# Trap_PCB_SMT2024.net
KiCad netlist of a schematic drawn in Altium Designer
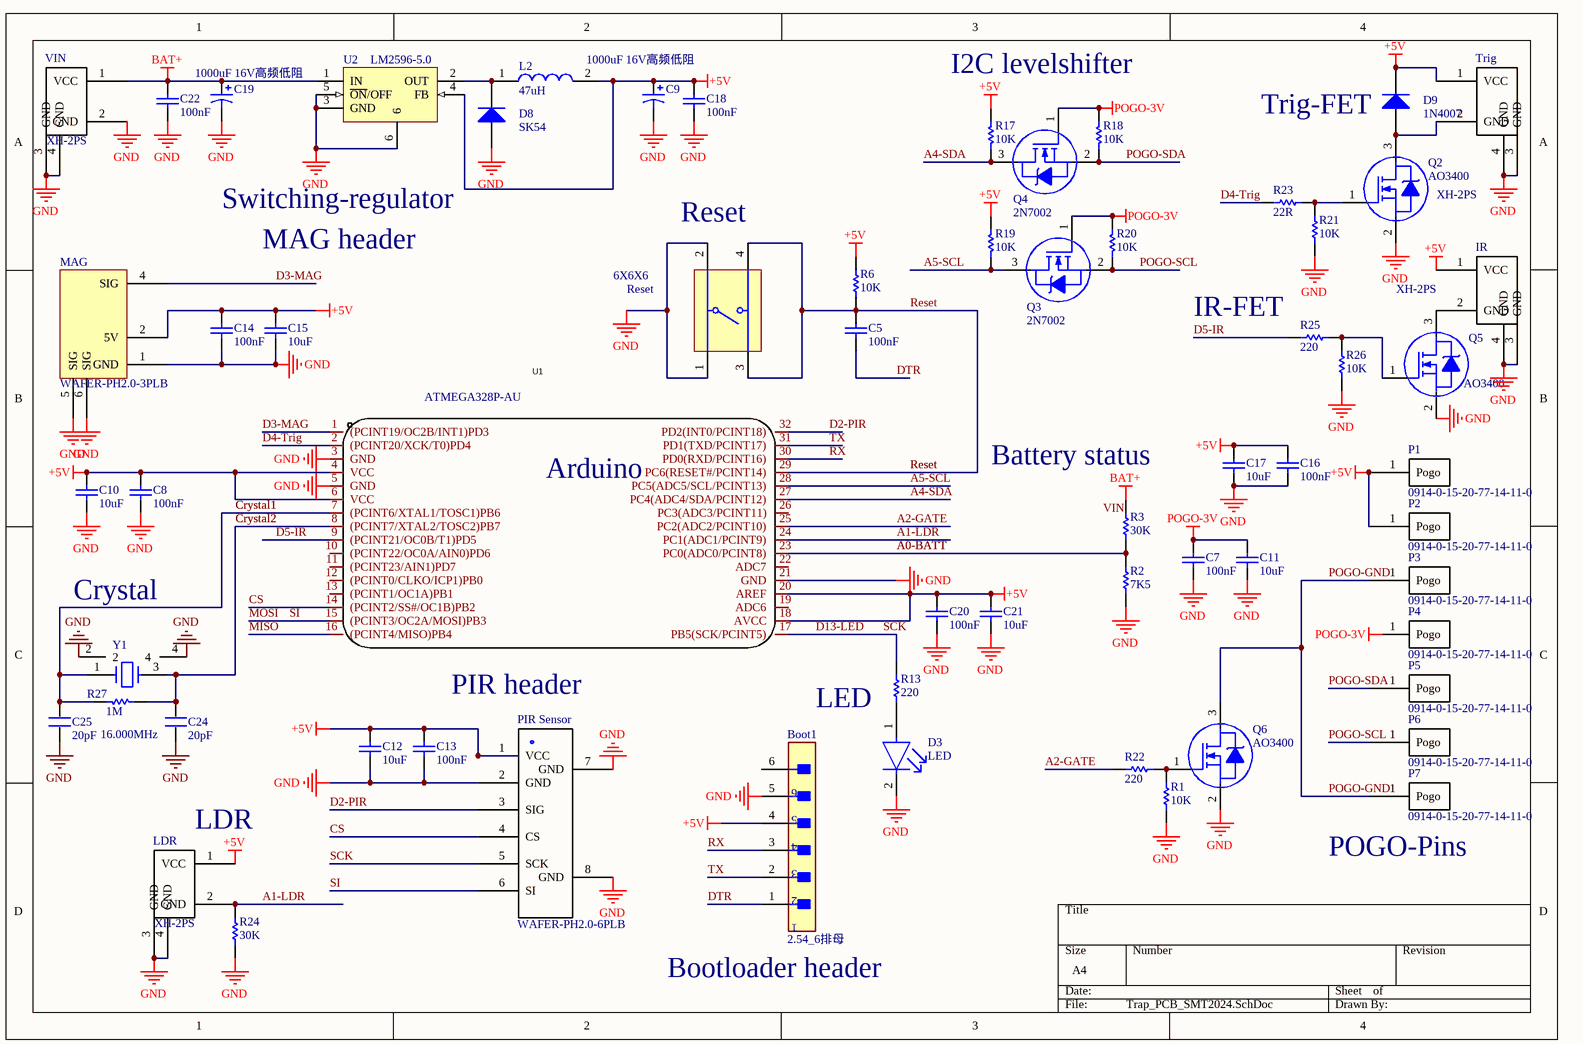
[diagram p0: Trap_PCB_SMT2024.SchDoc]

(export (version "E")
  (design (tool "Eeschema 10.0.6"))
  (components
    (comp (ref "Boot1")
      (value "2.54_6排母")
      (footprint "FP-SWR25X-NRTC-S06-ST-BA-MFG")
      (description "CONN HEADER VERT 6POS 2.54MM")
      (fields
        (field (name "OCTOPART") "https://octopart.com/swr25x-nrtc-s06-st-ba-sullins-20912730")
        (field (name "MANUFACTURER") "Sullins")
      )
      (libsource (lib "*") (part "f2cb566baf1c37ab5a3b8e90bbeafd6"))
    )
    (comp (ref "C5")
      (value "100nF")
      (footprint "0603C")
      (description "Capacitor, Ceramic, 22 pF, +/-10 %, 100 V, -55 to 125 degC, 2-Pin THD, RoHS, Bulk")
      (libsource (lib "*") (part "CAP-NP-2"))
    )
    (comp (ref "C7")
      (value "100nF")
      (footprint "0603C")
      (description "Capacitor, Ceramic, 22 pF, +/-10 %, 100 V, -55 to 125 degC, 2-Pin THD, RoHS, Bulk")
      (libsource (lib "*") (part "CAP-NP-2"))
    )
    (comp (ref "C8")
      (value "100nF")
      (footprint "0603C")
      (description "Capacitor, Ceramic, 22 pF, +/-10 %, 100 V, -55 to 125 degC, 2-Pin THD, RoHS, Bulk")
      (libsource (lib "*") (part "CAP-NP-2"))
    )
    (comp (ref "C9")
      (value "1000uF 16V高频低阻")
      (footprint "CAP-SMD_BD10.0-L10.3-W10.3-LS11.3-FD")
      (description "Polarized Capacitor (Surface Mount)")
      (fields (field (name "PUBLISHER") "Altium Limited"))
      (libsource (lib "Miscellaneous Devices") (part "Cap Pol3"))
    )
    (comp (ref "C10")
      (value "10uF")
      (footprint "0603C")
      (description "Capacitor, Ceramic, 22 pF, +/-10 %, 100 V, -55 to 125 degC, 2-Pin THD, RoHS, Bulk")
      (libsource (lib "*") (part "CAP-NP-2"))
    )
    (comp (ref "C11")
      (value "10uF")
      (footprint "0603C")
      (description "Capacitor, Ceramic, 22 pF, +/-10 %, 100 V, -55 to 125 degC, 2-Pin THD, RoHS, Bulk")
      (libsource (lib "*") (part "CAP-NP-2"))
    )
    (comp (ref "C12")
      (value "10uF")
      (footprint "0603C")
      (description "Capacitor, Ceramic, 22 pF, +/-10 %, 100 V, -55 to 125 degC, 2-Pin THD, RoHS, Bulk")
      (libsource (lib "*") (part "CAP-NP-2"))
    )
    (comp (ref "C13")
      (value "100nF")
      (footprint "0603C")
      (description "Capacitor, Ceramic, 22 pF, +/-10 %, 100 V, -55 to 125 degC, 2-Pin THD, RoHS, Bulk")
      (libsource (lib "*") (part "CAP-NP-2"))
    )
    (comp (ref "C14")
      (value "100nF")
      (footprint "0603C")
      (description "Capacitor, Ceramic, 22 pF, +/-10 %, 100 V, -55 to 125 degC, 2-Pin THD, RoHS, Bulk")
      (libsource (lib "*") (part "CAP-NP-2"))
    )
    (comp (ref "C15")
      (value "10uF")
      (footprint "0603C")
      (description "Capacitor, Ceramic, 22 pF, +/-10 %, 100 V, -55 to 125 degC, 2-Pin THD, RoHS, Bulk")
      (libsource (lib "*") (part "CAP-NP-2"))
    )
    (comp (ref "C16")
      (value "100nF")
      (footprint "0603C")
      (description "Capacitor, Ceramic, 22 pF, +/-10 %, 100 V, -55 to 125 degC, 2-Pin THD, RoHS, Bulk")
      (libsource (lib "*") (part "CAP-NP-2"))
    )
    (comp (ref "C17")
      (value "10uF")
      (footprint "0603C")
      (description "Capacitor, Ceramic, 22 pF, +/-10 %, 100 V, -55 to 125 degC, 2-Pin THD, RoHS, Bulk")
      (libsource (lib "*") (part "CAP-NP-2"))
    )
    (comp (ref "C18")
      (value "100nF")
      (footprint "0603C")
      (description "贴片")
      (libsource (lib "Schlib1") (part "电容"))
    )
    (comp (ref "C19")
      (value "1000uF 16V高频低阻")
      (footprint "CAP-SMD_BD10.0-L10.3-W10.3-LS11.3-FD")
      (description "Polarized Capacitor (Surface Mount)")
      (fields (field (name "PUBLISHER") "Altium Limited"))
      (libsource (lib "Miscellaneous Devices") (part "Cap Pol3"))
    )
    (comp (ref "C20")
      (value "100nF")
      (footprint "0603C")
      (description "Capacitor, Ceramic, 22 pF, +/-10 %, 100 V, -55 to 125 degC, 2-Pin THD, RoHS, Bulk")
      (libsource (lib "*") (part "CAP-NP-2"))
    )
    (comp (ref "C21")
      (value "10uF")
      (footprint "0603C")
      (description "Capacitor, Ceramic, 22 pF, +/-10 %, 100 V, -55 to 125 degC, 2-Pin THD, RoHS, Bulk")
      (libsource (lib "*") (part "CAP-NP-2"))
    )
    (comp (ref "C22")
      (value "100nF")
      (footprint "0603C")
      (description "贴片")
      (libsource (lib "Schlib1") (part "电容"))
    )
    (comp (ref "C24") (value "20pF") (footprint "0603C") (libsource (lib "*") (part "C")))
    (comp (ref "C25") (value "20pF") (footprint "0603C") (libsource (lib "*") (part "C")))
    (comp (ref "D3")
      (value "LED")
      (footprint "0603LED")
      (description "LED YELLOW DIFFUSED T-1 T/H")
      (fields (field (name "MANUFACTURER") "Broadcom"))
      (libsource (lib "*") (part "8706943c75ba83719d021d2fdc84c58"))
    )
    (comp (ref "D8")
      (value "SK54")
      (footprint "SMB-K")
      (description "Default Diode")
      (fields (field (name "PUBLISHER") "Altium Limited"))
      (libsource (lib "*") (part "Diode"))
    )
    (comp (ref "D9")
      (value "1N4007")
      (footprint "SMA")
      (description "Default Diode")
      (fields (field (name "PUBLISHER") "Altium Limited"))
      (libsource (lib "*") (part "Diode"))
    )
    (comp (ref "IR") (value "XH-2PS") (footprint "CNS_2.5-2") (libsource (lib "*") (part "JST HXP2")))
    (comp (ref "L2")
      (value "47uH")
      (footprint "L10.8X10")
      (description "Inductor")
      (fields (field (name "MANUFACTURER_PART_NUMBER") "SPM6545VT-100M-D"))
      (libsource (lib "*") (part "SPM6545VT-100M-D"))
    )
    (comp (ref "LDR") (value "XH-2PS") (footprint "CNS_2.5-2") (libsource (lib "*") (part "JST HXP2")))
    (comp (ref "MAG")
      (value "WAFER-PH2.0-3PLB")
      (footprint "CNS-2.0-4")
      (libsource (lib "*") (part "MAG Sensor"))
    )
    (comp (ref "P1")
      (value "0914-0-15-20-77-14-11-0")
      (footprint "0914-0-15-20-77-14-11-0")
      (description "CONTACT SPRING LOADED T/H GOLD")
      (libsource (lib "*") (part "0914-0-15-20-77-14-11-0"))
    )
    (comp (ref "P2")
      (value "0914-0-15-20-77-14-11-0")
      (footprint "0914-0-15-20-77-14-11-0")
      (description "CONTACT SPRING LOADED T/H GOLD")
      (libsource (lib "*") (part "0914-0-15-20-77-14-11-0"))
    )
    (comp (ref "P3")
      (value "0914-0-15-20-77-14-11-0")
      (footprint "0914-0-15-20-77-14-11-0")
      (description "CONTACT SPRING LOADED T/H GOLD")
      (libsource (lib "*") (part "0914-0-15-20-77-14-11-0"))
    )
    (comp (ref "P4")
      (value "0914-0-15-20-77-14-11-0")
      (footprint "0914-0-15-20-77-14-11-0")
      (description "CONTACT SPRING LOADED T/H GOLD")
      (libsource (lib "*") (part "0914-0-15-20-77-14-11-0"))
    )
    (comp (ref "P5")
      (value "0914-0-15-20-77-14-11-0")
      (footprint "0914-0-15-20-77-14-11-0")
      (description "CONTACT SPRING LOADED T/H GOLD")
      (libsource (lib "*") (part "0914-0-15-20-77-14-11-0"))
    )
    (comp (ref "P6")
      (value "0914-0-15-20-77-14-11-0")
      (footprint "0914-0-15-20-77-14-11-0")
      (description "CONTACT SPRING LOADED T/H GOLD")
      (libsource (lib "*") (part "0914-0-15-20-77-14-11-0"))
    )
    (comp (ref "P7")
      (value "0914-0-15-20-77-14-11-0")
      (footprint "0914-0-15-20-77-14-11-0")
      (description "CONTACT SPRING LOADED T/H GOLD")
      (libsource (lib "*") (part "0914-0-15-20-77-14-11-0"))
    )
    (comp (ref "PIR Sensor")
      (value "WAFER-PH2.0-6PLB")
      (footprint "CNS-2.0-6")
      (libsource (lib "*") (part "JST - PH-6p - 2.0mm"))
    )
    (comp (ref "Q2") (value "AO3400") (footprint "SOT-23") (libsource (lib "Schlib1") (part "IRF640N")))
    (comp (ref "Q3") (value "2N7002") (footprint "SOT-23") (libsource (lib "") (part "IRF640N_1")))
    (comp (ref "Q4") (value "2N7002") (footprint "SOT-23") (libsource (lib "") (part "IRF640N_1")))
    (comp (ref "Q5") (value "AO3400") (footprint "SOT-23") (libsource (lib "Schlib1") (part "IRF640N")))
    (comp (ref "Q6") (value "AO3400") (footprint "SOT-23") (libsource (lib "Schlib1") (part "IRF640N")))
    (comp (ref "R1")
      (value "10K")
      (footprint "0603R")
      (fields (field (name "TOLERANCE") "±5%"))
      (libsource (lib "*") (part "RES-2"))
    )
    (comp (ref "R2")
      (value "7K5")
      (footprint "0603R")
      (fields (field (name "TOLERANCE") "±5%"))
      (libsource (lib "*") (part "RES-2"))
    )
    (comp (ref "R3")
      (value "30K")
      (footprint "0603R")
      (fields (field (name "TOLERANCE") "±5%"))
      (libsource (lib "*") (part "RES-2"))
    )
    (comp (ref "R6")
      (value "10K")
      (footprint "0603R")
      (fields (field (name "TOLERANCE") "±5%"))
      (libsource (lib "*") (part "RES-2"))
    )
    (comp (ref "R13")
      (value "220")
      (footprint "0603R")
      (fields (field (name "TOLERANCE") "±5%"))
      (libsource (lib "*") (part "RES-2"))
    )
    (comp (ref "R17")
      (value "10K")
      (footprint "0603R")
      (fields (field (name "TOLERANCE") "±5%"))
      (libsource (lib "*") (part "RES-2"))
    )
    (comp (ref "R18")
      (value "10K")
      (footprint "0603R")
      (fields (field (name "TOLERANCE") "±5%"))
      (libsource (lib "*") (part "RES-2"))
    )
    (comp (ref "R19")
      (value "10K")
      (footprint "0603R")
      (fields (field (name "TOLERANCE") "±5%"))
      (libsource (lib "*") (part "RES-2"))
    )
    (comp (ref "R20")
      (value "10K")
      (footprint "0603R")
      (fields (field (name "TOLERANCE") "±5%"))
      (libsource (lib "*") (part "RES-2"))
    )
    (comp (ref "R21")
      (value "10K")
      (footprint "0603R")
      (fields (field (name "TOLERANCE") "±5%"))
      (libsource (lib "*") (part "RES-2"))
    )
    (comp (ref "R22")
      (value "220")
      (footprint "0603R")
      (fields (field (name "TOLERANCE") "±5%"))
      (libsource (lib "*") (part "RES-2"))
    )
    (comp (ref "R23")
      (value "22R")
      (footprint "0603R")
      (fields (field (name "TOLERANCE") "±5%"))
      (libsource (lib "*") (part "RES-2"))
    )
    (comp (ref "R24")
      (value "30K")
      (footprint "0603R")
      (fields (field (name "TOLERANCE") "±5%"))
      (libsource (lib "*") (part "RES-2"))
    )
    (comp (ref "R25")
      (value "220")
      (footprint "0603R")
      (fields (field (name "TOLERANCE") "±5%"))
      (libsource (lib "*") (part "RES-2"))
    )
    (comp (ref "R26")
      (value "10K")
      (footprint "0603R")
      (fields (field (name "TOLERANCE") "±5%"))
      (libsource (lib "*") (part "RES-2"))
    )
    (comp (ref "R27")
      (value "1M")
      (footprint "0603R")
      (description "Resistor")
      (fields (field (name "PUBLISHER") "Altium Limited"))
      (libsource (lib "Miscellaneous Devices") (part "Res1"))
    )
    (comp (ref "Reset")
      (value "6X6X6")
      (footprint "SW-4P-6X6")
      (description "Tactile Switch, SPST-NO, 0.05 A, 5 to 24 V, -25 to 70 degC, 4-Pin THD, RoHS, Bulk")
      (libsource (lib "*") (part "SW-SPST-4_A"))
    )
    (comp (ref "Trig") (value "XH-2PS") (footprint "CNS_2.5-2") (libsource (lib "*") (part "JST HXP2")))
    (comp (ref "U1")
      (value "ATMEGA328P-AU")
      (footprint "TQFP-32_L7.0-W7.0-P0.80-LS9.0-BL")
      (libsource (lib "altium-import") (part "root_0_ATMEGA328P-AU_"))
    )
    (comp (ref "U2")
      (value "LM2596-5.0")
      (footprint "TO263-5")
      (description "Simple Switcher Power Converter 150 kHz 3A Step Down Voltage Regulator")
      (fields (field (name "PUBLISHER") "Altium Limited"))
      (libsource (lib "NSC Power Mgt Switching Regulator") (part "LM2596T-5.0"))
    )
    (comp (ref "VIN") (value "XH-2PS") (footprint "CNS_2.5-2") (libsource (lib "*") (part "JST HXP2")))
    (comp (ref "Y1")
      (value "16.000MHz")
      (footprint "X3225")
      (description "R25010031/工业C/消费A/晶体振荡器/8.000M/20pF/±30ppm/49USM/ROHS/-10℃~+70℃")
      (libsource (lib "R25_IC") (part "R25010031"))
    )
  )
  (nets
    (net (code "1") (name "+5V") (class "Default")
      (node (ref "Boot1") (pin "4") (pinfunction "4_4") (pintype "passive"))
      (node (ref "C10") (pin "2") (pinfunction "2_2") (pintype "passive"))
      (node (ref "C12") (pin "2") (pinfunction "2_2") (pintype "passive"))
      (node (ref "C13") (pin "2") (pinfunction "2_2") (pintype "passive"))
      (node (ref "C14") (pin "2") (pinfunction "2_2") (pintype "passive"))
      (node (ref "C15") (pin "2") (pinfunction "2_2") (pintype "passive"))
      (node (ref "C16") (pin "2") (pinfunction "2_2") (pintype "passive"))
      (node (ref "C17") (pin "2") (pinfunction "2_2") (pintype "passive"))
      (node (ref "C18") (pin "1") (pinfunction "1_1") (pintype "passive"))
      (node (ref "C20") (pin "2") (pinfunction "2_2") (pintype "passive"))
      (node (ref "C21") (pin "2") (pinfunction "2_2") (pintype "passive"))
      (node (ref "C8") (pin "2") (pinfunction "2_2") (pintype "passive"))
      (node (ref "C9") (pin "1") (pinfunction "1_1") (pintype "passive"))
      (node (ref "D9") (pin "2") (pinfunction "K_2") (pintype "passive"))
      (node (ref "IR") (pin "1") (pinfunction "VCC_1") (pintype "passive"))
      (node (ref "L2") (pin "2") (pinfunction "2_2") (pintype "passive"))
      (node (ref "LDR") (pin "1") (pinfunction "VCC_1") (pintype "passive"))
      (node (ref "MAG") (pin "2") (pinfunction "5V_2") (pintype "passive"))
      (node (ref "P1") (pin "1") (pinfunction "Pogo_1") (pintype "passive"))
      (node (ref "P2") (pin "1") (pinfunction "Pogo_1") (pintype "passive"))
      (node (ref "PIR Sensor") (pin "1") (pinfunction "VCC_1") (pintype "passive"))
      (node (ref "R17") (pin "2") (pinfunction "2_2") (pintype "passive"))
      (node (ref "R19") (pin "2") (pinfunction "2_2") (pintype "passive"))
      (node (ref "R6") (pin "1") (pinfunction "1_1") (pintype "passive"))
      (node (ref "Trig") (pin "1") (pinfunction "VCC_1") (pintype "passive"))
      (node (ref "U1") (pin "18") (pinfunction "AVCC_18") (pintype "passive"))
      (node (ref "U1") (pin "20") (pinfunction "AREF_20") (pintype "passive"))
      (node (ref "U1") (pin "4") (pinfunction "VCC_4") (pintype "passive"))
      (node (ref "U1") (pin "6") (pinfunction "VCC_6") (pintype "passive"))
      (node (ref "U2") (pin "4") (pinfunction "FB_4") (pintype "input"))
    )
    (net (code "2") (name "/A0-BATT") (class "Default")
      (node (ref "R2") (pin "1") (pinfunction "1_1") (pintype "passive"))
      (node (ref "R3") (pin "2") (pinfunction "2_2") (pintype "passive"))
      (node (ref "U1") (pin "23") (pinfunction "PC0(ADC0/PCINT8)_23") (pintype "passive"))
    )
    (net (code "3") (name "/A1-LDR") (class "Default")
      (node (ref "LDR") (pin "2") (pinfunction "GND_2") (pintype "passive"))
      (node (ref "R24") (pin "2") (pinfunction "2_2") (pintype "passive"))
      (node (ref "U1") (pin "24") (pinfunction "PC1(ADC1/PCINT9)_24") (pintype "passive"))
    )
    (net (code "4") (name "/A2-GATE") (class "Default")
      (node (ref "R22") (pin "2") (pinfunction "2_2") (pintype "passive"))
      (node (ref "U1") (pin "25") (pinfunction "PC2(ADC2/PCINT10)_25") (pintype "passive"))
    )
    (net (code "5") (name "/A4-SDA") (class "Default")
      (node (ref "Q4") (pin "3") (pinfunction "3_3") (pintype "passive"))
      (node (ref "R17") (pin "1") (pinfunction "1_1") (pintype "passive"))
      (node (ref "U1") (pin "27") (pinfunction "PC4(ADC4/SDA/PCINT12)_27") (pintype "passive"))
    )
    (net (code "6") (name "/A5-SCL") (class "Default")
      (node (ref "Q3") (pin "3") (pinfunction "3_3") (pintype "passive"))
      (node (ref "R19") (pin "1") (pinfunction "1_1") (pintype "passive"))
      (node (ref "U1") (pin "28") (pinfunction "PC5(ADC5/SCL/PCINT13)_28") (pintype "passive"))
    )
    (net (code "7") (name "/CS") (class "Default")
      (node (ref "PIR Sensor") (pin "4") (pinfunction "CS_4") (pintype "passive"))
      (node (ref "U1") (pin "14") (pinfunction "(PCINT2/SS#/OC1B)PB2_14") (pintype "passive"))
    )
    (net (code "8") (name "/Crystal1") (class "Default")
      (node (ref "C25") (pin "2") (pintype "passive"))
      (node (ref "R27") (pin "2") (pinfunction "2_2") (pintype "passive"))
      (node (ref "U1") (pin "7") (pinfunction "(PCINT6/XTAL1/TOSC1)PB6_7") (pintype "passive"))
      (node (ref "Y1") (pin "1") (pinfunction "1_1") (pintype "passive"))
    )
    (net (code "9") (name "/Crystal2") (class "Default")
      (node (ref "C24") (pin "2") (pintype "passive"))
      (node (ref "R27") (pin "1") (pinfunction "1_1") (pintype "passive"))
      (node (ref "U1") (pin "8") (pinfunction "(PCINT7/XTAL2/TOSC2)PB7_8") (pintype "passive"))
      (node (ref "Y1") (pin "3") (pinfunction "3_3") (pintype "passive"))
    )
    (net (code "10") (name "/D2-PIR") (class "Default")
      (node (ref "PIR Sensor") (pin "3") (pinfunction "SIG_3") (pintype "passive"))
      (node (ref "U1") (pin "32") (pinfunction "PD2(INT0/PCINT18)_32") (pintype "passive"))
    )
    (net (code "11") (name "/D3-MAG") (class "Default")
      (node (ref "MAG") (pin "4") (pinfunction "SIG_4") (pintype "passive"))
      (node (ref "U1") (pin "1") (pinfunction "(PCINT19/OC2B/INT1)PD3_1") (pintype "passive"))
    )
    (net (code "12") (name "/D4-Trig") (class "Default")
      (node (ref "R23") (pin "2") (pinfunction "2_2") (pintype "passive"))
      (node (ref "U1") (pin "2") (pinfunction "(PCINT20/XCK/T0)PD4_2") (pintype "passive"))
    )
    (net (code "13") (name "/D5-IR") (class "Default")
      (node (ref "R25") (pin "2") (pinfunction "2_2") (pintype "passive"))
      (node (ref "U1") (pin "9") (pinfunction "(PCINT21/OC0B/T1)PD5_9") (pintype "passive"))
    )
    (net (code "14") (name "/D13-LED") (class "Default")
      (node (ref "PIR Sensor") (pin "5") (pinfunction "SCK_5") (pintype "passive"))
      (node (ref "R13") (pin "2") (pinfunction "2_2") (pintype "passive"))
      (node (ref "U1") (pin "17") (pinfunction "PB5(SCK/PCINT5)_17") (pintype "passive"))
    )
    (net (code "15") (name "/DTR") (class "Default")
      (node (ref "Boot1") (pin "1") (pinfunction "1_1") (pintype "passive"))
      (node (ref "C5") (pin "1") (pinfunction "1_1") (pintype "passive"))
    )
    (net (code "16") (name "/MISO") (class "Default")
      (node (ref "U1") (pin "16") (pinfunction "(PCINT4/MISO)PB4_16") (pintype "passive"))
    )
    (net (code "17") (name "/MOSI") (class "Default")
      (node (ref "PIR Sensor") (pin "6") (pinfunction "SI_6") (pintype "passive"))
      (node (ref "U1") (pin "15") (pinfunction "(PCINT3/OC2A/MOSI)PB3_15") (pintype "passive"))
    )
    (net (code "18") (name "/POGO-GND") (class "Default")
      (node (ref "P3") (pin "1") (pinfunction "Pogo_1") (pintype "passive"))
      (node (ref "P7") (pin "1") (pinfunction "Pogo_1") (pintype "passive"))
      (node (ref "Q6") (pin "3") (pinfunction "3_3") (pintype "passive"))
    )
    (net (code "19") (name "/POGO-SCL") (class "Default")
      (node (ref "P6") (pin "1") (pinfunction "Pogo_1") (pintype "passive"))
      (node (ref "Q3") (pin "2") (pinfunction "2_2") (pintype "passive"))
      (node (ref "R20") (pin "1") (pinfunction "1_1") (pintype "passive"))
    )
    (net (code "20") (name "/POGO-SDA") (class "Default")
      (node (ref "P5") (pin "1") (pinfunction "Pogo_1") (pintype "passive"))
      (node (ref "Q4") (pin "2") (pinfunction "2_2") (pintype "passive"))
      (node (ref "R18") (pin "1") (pinfunction "1_1") (pintype "passive"))
    )
    (net (code "21") (name "/RX") (class "Default")
      (node (ref "Boot1") (pin "3") (pinfunction "3_3") (pintype "passive"))
      (node (ref "U1") (pin "30") (pinfunction "PD0(RXD/PCINT16)_30") (pintype "passive"))
    )
    (net (code "22") (name "/Reset") (class "Default")
      (node (ref "C5") (pin "2") (pinfunction "2_2") (pintype "passive"))
      (node (ref "R6") (pin "2") (pinfunction "2_2") (pintype "passive"))
      (node (ref "Reset") (pin "3") (pinfunction "3_3") (pintype "passive"))
      (node (ref "Reset") (pin "4") (pinfunction "4_4") (pintype "passive"))
      (node (ref "U1") (pin "29") (pinfunction "PC6(RESET#/PCINT14)_29") (pintype "passive"))
    )
    (net (code "23") (name "/TX") (class "Default")
      (node (ref "Boot1") (pin "2") (pinfunction "2_2") (pintype "passive"))
      (node (ref "U1") (pin "31") (pinfunction "PD1(TXD/PCINT17)_31") (pintype "passive"))
    )
    (net (code "24") (name "BAT+") (class "Default")
      (node (ref "C19") (pin "1") (pinfunction "1_1") (pintype "passive"))
      (node (ref "C22") (pin "1") (pinfunction "1_1") (pintype "passive"))
      (node (ref "R3") (pin "1") (pinfunction "1_1") (pintype "passive"))
      (node (ref "U2") (pin "1") (pinfunction "IN_1") (pintype "power_in"))
      (node (ref "VIN") (pin "1") (pinfunction "VCC_1") (pintype "passive"))
    )
    (net (code "25") (name "GND") (class "Default")
      (node (ref "Boot1") (pin "5") (pinfunction "5_5") (pintype "passive"))
      (node (ref "C10") (pin "1") (pinfunction "1_1") (pintype "passive"))
      (node (ref "C11") (pin "1") (pinfunction "1_1") (pintype "passive"))
      (node (ref "C12") (pin "1") (pinfunction "1_1") (pintype "passive"))
      (node (ref "C13") (pin "1") (pinfunction "1_1") (pintype "passive"))
      (node (ref "C14") (pin "1") (pinfunction "1_1") (pintype "passive"))
      (node (ref "C15") (pin "1") (pinfunction "1_1") (pintype "passive"))
      (node (ref "C16") (pin "1") (pinfunction "1_1") (pintype "passive"))
      (node (ref "C17") (pin "1") (pinfunction "1_1") (pintype "passive"))
      (node (ref "C18") (pin "2") (pinfunction "2_2") (pintype "passive"))
      (node (ref "C19") (pin "2") (pinfunction "2_2") (pintype "passive"))
      (node (ref "C20") (pin "1") (pinfunction "1_1") (pintype "passive"))
      (node (ref "C21") (pin "1") (pinfunction "1_1") (pintype "passive"))
      (node (ref "C22") (pin "2") (pinfunction "2_2") (pintype "passive"))
      (node (ref "C24") (pin "1") (pintype "passive"))
      (node (ref "C25") (pin "1") (pintype "passive"))
      (node (ref "C7") (pin "1") (pinfunction "1_1") (pintype "passive"))
      (node (ref "C8") (pin "1") (pinfunction "1_1") (pintype "passive"))
      (node (ref "C9") (pin "2") (pinfunction "2_2") (pintype "passive"))
      (node (ref "D3") (pin "2") (pinfunction "A_2") (pintype "passive"))
      (node (ref "D8") (pin "1") (pinfunction "A_1") (pintype "passive"))
      (node (ref "IR") (pin "3") (pinfunction "GND_3") (pintype "passive"))
      (node (ref "IR") (pin "4") (pinfunction "GND_4") (pintype "passive"))
      (node (ref "LDR") (pin "3") (pinfunction "GND_3") (pintype "passive"))
      (node (ref "LDR") (pin "4") (pinfunction "GND_4") (pintype "passive"))
      (node (ref "MAG") (pin "1") (pinfunction "GND_1") (pintype "passive"))
      (node (ref "MAG") (pin "5") (pinfunction "SIG_5") (pintype "passive"))
      (node (ref "MAG") (pin "6") (pinfunction "SIG_6") (pintype "passive"))
      (node (ref "PIR Sensor") (pin "2") (pinfunction "GND_2") (pintype "passive"))
      (node (ref "PIR Sensor") (pin "7") (pinfunction "GND_7") (pintype "passive"))
      (node (ref "PIR Sensor") (pin "8") (pinfunction "GND_8") (pintype "passive"))
      (node (ref "Q2") (pin "2") (pinfunction "2_2") (pintype "passive"))
      (node (ref "Q5") (pin "2") (pinfunction "2_2") (pintype "passive"))
      (node (ref "Q6") (pin "2") (pinfunction "2_2") (pintype "passive"))
      (node (ref "R1") (pin "1") (pinfunction "1_1") (pintype "passive"))
      (node (ref "R2") (pin "2") (pinfunction "2_2") (pintype "passive"))
      (node (ref "R21") (pin "1") (pinfunction "1_1") (pintype "passive"))
      (node (ref "R24") (pin "1") (pinfunction "1_1") (pintype "passive"))
      (node (ref "R26") (pin "1") (pinfunction "1_1") (pintype "passive"))
      (node (ref "Reset") (pin "1") (pinfunction "1_1") (pintype "passive"))
      (node (ref "Reset") (pin "2") (pinfunction "2_2") (pintype "passive"))
      (node (ref "Trig") (pin "3") (pinfunction "GND_3") (pintype "passive"))
      (node (ref "Trig") (pin "4") (pinfunction "GND_4") (pintype "passive"))
      (node (ref "U1") (pin "21") (pinfunction "GND_21") (pintype "passive"))
      (node (ref "U1") (pin "3") (pinfunction "GND_3") (pintype "passive"))
      (node (ref "U1") (pin "5") (pinfunction "GND_5") (pintype "passive"))
      (node (ref "U2") (pin "3") (pinfunction "GND_3") (pintype "power_in"))
      (node (ref "U2") (pin "5") (pinfunction "~{ON}/OFF_5") (pintype "input"))
      (node (ref "U2") (pin "6") (pinfunction "6_6") (pintype "power_in"))
      (node (ref "VIN") (pin "2") (pinfunction "GND_2") (pintype "passive"))
      (node (ref "VIN") (pin "3") (pinfunction "GND_3") (pintype "passive"))
      (node (ref "VIN") (pin "4") (pinfunction "GND_4") (pintype "passive"))
      (node (ref "Y1") (pin "2") (pinfunction "2_2") (pintype "passive"))
      (node (ref "Y1") (pin "4") (pinfunction "4_4") (pintype "passive"))
    )
    (net (code "26") (name "Net-(D3-C)") (class "Default")
      (node (ref "D3") (pin "1") (pinfunction "C_1") (pintype "passive"))
      (node (ref "R13") (pin "1") (pinfunction "1_1") (pintype "passive"))
    )
    (net (code "27") (name "Net-(D8-K)") (class "Default")
      (node (ref "D8") (pin "2") (pinfunction "K_2") (pintype "passive"))
      (node (ref "L2") (pin "1") (pinfunction "1_1") (pintype "passive"))
      (node (ref "U2") (pin "2") (pinfunction "OUT_2") (pintype "power_in"))
    )
    (net (code "28") (name "Net-(D9-A)") (class "Default")
      (node (ref "D9") (pin "1") (pinfunction "A_1") (pintype "passive"))
      (node (ref "Q2") (pin "3") (pinfunction "3_3") (pintype "passive"))
      (node (ref "Trig") (pin "2") (pinfunction "GND_2") (pintype "passive"))
    )
    (net (code "29") (name "Net-(IR-GND-Pad2)") (class "Default")
      (node (ref "IR") (pin "2") (pinfunction "GND_2") (pintype "passive"))
      (node (ref "Q5") (pin "3") (pinfunction "3_3") (pintype "passive"))
    )
    (net (code "30") (name "Net-(Q2-Pad1)") (class "Default")
      (node (ref "Q2") (pin "1") (pinfunction "1_1") (pintype "passive"))
      (node (ref "R21") (pin "2") (pinfunction "2_2") (pintype "passive"))
      (node (ref "R23") (pin "1") (pinfunction "1_1") (pintype "passive"))
    )
    (net (code "31") (name "Net-(Q5-Pad1)") (class "Default")
      (node (ref "Q5") (pin "1") (pinfunction "1_1") (pintype "passive"))
      (node (ref "R25") (pin "1") (pinfunction "1_1") (pintype "passive"))
      (node (ref "R26") (pin "2") (pinfunction "2_2") (pintype "passive"))
    )
    (net (code "32") (name "Net-(Q6-Pad1)") (class "Default")
      (node (ref "Q6") (pin "1") (pinfunction "1_1") (pintype "passive"))
      (node (ref "R1") (pin "2") (pinfunction "2_2") (pintype "passive"))
      (node (ref "R22") (pin "1") (pinfunction "1_1") (pintype "passive"))
    )
    (net (code "33") (name "POGO-3V") (class "Default")
      (node (ref "C11") (pin "2") (pinfunction "2_2") (pintype "passive"))
      (node (ref "C7") (pin "2") (pinfunction "2_2") (pintype "passive"))
      (node (ref "P4") (pin "1") (pinfunction "Pogo_1") (pintype "passive"))
      (node (ref "Q3") (pin "1") (pinfunction "1_1") (pintype "passive"))
      (node (ref "Q4") (pin "1") (pinfunction "1_1") (pintype "passive"))
      (node (ref "R18") (pin "2") (pinfunction "2_2") (pintype "passive"))
      (node (ref "R20") (pin "2") (pinfunction "2_2") (pintype "passive"))
    )
    (net (code "34") (name "unconnected-(Boot1-Pad6)") (class "Default")
      (node (ref "Boot1") (pin "6") (pinfunction "6_6") (pintype "passive"))
    )
    (net (code "35") (name "unconnected-(U1-(PCINT0{slash}CLKO{slash}ICP1)PB0-Pad12)") (class "Default")
      (node (ref "U1") (pin "12") (pinfunction "(PCINT0/CLKO/ICP1)PB0_12") (pintype "passive"))
    )
    (net (code "36") (name "unconnected-(U1-(PCINT1{slash}OC1A)PB1-Pad13)") (class "Default")
      (node (ref "U1") (pin "13") (pinfunction "(PCINT1/OC1A)PB1_13") (pintype "passive"))
    )
    (net (code "37") (name "unconnected-(U1-(PCINT22{slash}OC0A{slash}AIN0)PD6-Pad10)") (class "Default")
      (node (ref "U1") (pin "10") (pinfunction "(PCINT22/OC0A/AIN0)PD6_10") (pintype "passive"))
    )
    (net (code "38") (name "unconnected-(U1-(PCINT23{slash}AIN1)PD7-Pad11)") (class "Default")
      (node (ref "U1") (pin "11") (pinfunction "(PCINT23/AIN1)PD7_11") (pintype "passive"))
    )
    (net (code "39") (name "unconnected-(U1-ADC6-Pad19)") (class "Default")
      (node (ref "U1") (pin "19") (pinfunction "ADC6_19") (pintype "passive"))
    )
    (net (code "40") (name "unconnected-(U1-ADC7-Pad22)") (class "Default")
      (node (ref "U1") (pin "22") (pinfunction "ADC7_22") (pintype "passive"))
    )
    (net (code "41") (name "unconnected-(U1-PC3(ADC3{slash}PCINT11)-Pad26)") (class "Default")
      (node (ref "U1") (pin "26") (pinfunction "PC3(ADC3/PCINT11)_26") (pintype "passive"))
    )
  )
)
